# SlaveInput.net
KiCad netlist of a schematic drawn in EAGLE
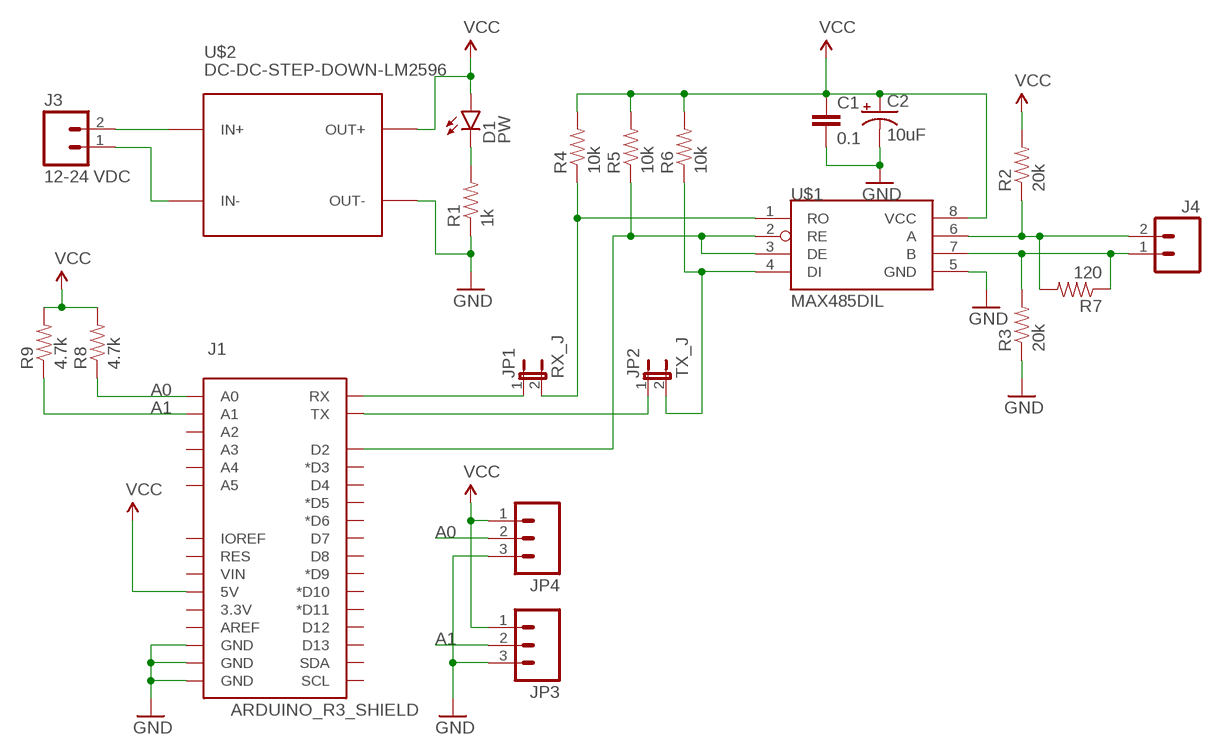
[diagram p0: schematic, sheet 1]

(export (version "E")
  (design (tool "Eeschema 10.0.6"))
  (components
    (comp (ref "C1")
      (value "0.1")
      (footprint "eagle-import:CAP-PTH-5MM")
      (libsource (lib "eagle-import") (part "CAPPTH1"))
    )
    (comp (ref "C2")
      (value "10uF")
      (footprint "eagle-import:CPOL-RADIAL-10UF-25V")
      (libsource (lib "eagle-import") (part "CAP_POLPTH2"))
    )
    (comp (ref "D1")
      (value "PW")
      (footprint "eagle-import:LED3MM")
      (libsource (lib "eagle-import") (part "LED3MM"))
    )
    (comp (ref "J1")
      (value "ARDUINO_R3_SHIELD")
      (footprint "eagle-import:UNO_R3_SHIELD")
      (libsource (lib "eagle-import") (part "ARDUINO_R3_SHIELD"))
    )
    (comp (ref "J3")
      (value "12-24 VDC")
      (footprint "eagle-import:SCREWTERMINAL-5MM-2")
      (libsource (lib "eagle-import") (part "M025MM"))
    )
    (comp (ref "J4")
      (value "M025MM")
      (footprint "eagle-import:SCREWTERMINAL-5MM-2")
      (libsource (lib "eagle-import") (part "M025MM"))
    )
    (comp (ref "JP1")
      (value "RX_J")
      (footprint "eagle-import:1X02")
      (libsource (lib "eagle-import") (part "JUMPER-2PTH"))
    )
    (comp (ref "JP2")
      (value "TX_J")
      (footprint "eagle-import:1X02")
      (libsource (lib "eagle-import") (part "JUMPER-2PTH"))
    )
    (comp (ref "JP3")
      (value "M03-SCREW-5MM")
      (footprint "eagle-import:SCREWTERMINAL-5MM-3")
      (libsource (lib "eagle-import") (part "M03-SCREW-5MM"))
    )
    (comp (ref "JP4")
      (value "M03-SCREW-5MM")
      (footprint "eagle-import:SCREWTERMINAL-5MM-3")
      (libsource (lib "eagle-import") (part "M03-SCREW-5MM"))
    )
    (comp (ref "R1")
      (value "1k")
      (footprint "eagle-import:AXIAL-0.3")
      (libsource (lib "eagle-import") (part "RESISTORAXIAL-0.3"))
    )
    (comp (ref "R2")
      (value "20k")
      (footprint "eagle-import:AXIAL-0.3")
      (libsource (lib "eagle-import") (part "RESISTORAXIAL-0.3"))
    )
    (comp (ref "R3")
      (value "20k")
      (footprint "eagle-import:AXIAL-0.3")
      (libsource (lib "eagle-import") (part "RESISTORAXIAL-0.3"))
    )
    (comp (ref "R4")
      (value "10k")
      (footprint "eagle-import:AXIAL-0.3")
      (libsource (lib "eagle-import") (part "RESISTORAXIAL-0.3"))
    )
    (comp (ref "R5")
      (value "10k")
      (footprint "eagle-import:AXIAL-0.3")
      (libsource (lib "eagle-import") (part "RESISTORAXIAL-0.3"))
    )
    (comp (ref "R6")
      (value "10k")
      (footprint "eagle-import:AXIAL-0.3")
      (libsource (lib "eagle-import") (part "RESISTORAXIAL-0.3"))
    )
    (comp (ref "R7")
      (value "120")
      (footprint "eagle-import:AXIAL-0.3")
      (libsource (lib "eagle-import") (part "RESISTORAXIAL-0.3"))
    )
    (comp (ref "R8")
      (value "4.7k")
      (footprint "eagle-import:AXIAL-0.3")
      (libsource (lib "eagle-import") (part "RESISTORAXIAL-0.3"))
    )
    (comp (ref "R9")
      (value "4.7k")
      (footprint "eagle-import:AXIAL-0.3")
      (libsource (lib "eagle-import") (part "RESISTORAXIAL-0.3"))
    )
    (comp (ref "U$1")
      (value "MAX485DIL")
      (footprint "eagle-import:DIL08")
      (libsource (lib "eagle-import") (part "MAX485DIL"))
    )
    (comp (ref "U$2")
      (value "DC-DC-STEP-DOWN-LM2596")
      (footprint "eagle-import:DC-DC-STEP-DOWN-LM2596")
      (libsource (lib "eagle-import") (part "DC-DC-STEP-DOWN-LM2596"))
    )
  )
  (nets
    (net (code "1") (name "/A0") (class "Default")
      (node (ref "J1") (pin "A0") (pinfunction "A0_A0") (pintype "bidirectional"))
      (node (ref "JP4") (pin "2") (pinfunction "2_2") (pintype "passive"))
      (node (ref "R8") (pin "P$1") (pinfunction "1_P$1") (pintype "passive"))
    )
    (net (code "2") (name "/A1") (class "Default")
      (node (ref "J1") (pin "A1") (pinfunction "A1_A1") (pintype "bidirectional"))
      (node (ref "JP3") (pin "2") (pinfunction "2_2") (pintype "passive"))
      (node (ref "R9") (pin "P$1") (pinfunction "1_P$1") (pintype "passive"))
    )
    (net (code "3") (name "GND") (class "Default")
      (node (ref "C1") (pin "2") (pinfunction "2_2") (pintype "passive"))
      (node (ref "C2") (pin "2") (pinfunction "-_2") (pintype "passive"))
      (node (ref "J1") (pin "GND@0") (pinfunction "GND_GND@0") (pintype "bidirectional"))
      (node (ref "J1") (pin "GND@1") (pinfunction "GND_GND@1") (pintype "bidirectional"))
      (node (ref "J1") (pin "GND@2") (pinfunction "GND_GND@2") (pintype "bidirectional"))
      (node (ref "JP3") (pin "3") (pinfunction "3_3") (pintype "passive"))
      (node (ref "JP4") (pin "3") (pinfunction "3_3") (pintype "passive"))
      (node (ref "R1") (pin "P$1") (pinfunction "1_P$1") (pintype "passive"))
      (node (ref "R3") (pin "P$1") (pinfunction "1_P$1") (pintype "passive"))
      (node (ref "U$1") (pin "5") (pinfunction "GND_5") (pintype "bidirectional"))
      (node (ref "U$2") (pin "OUT-") (pinfunction "OUT-_OUT-") (pintype "bidirectional"))
    )
    (net (code "4") (name "Net-(D1-C)") (class "Default")
      (node (ref "D1") (pin "K") (pinfunction "C_K") (pintype "passive"))
      (node (ref "R1") (pin "P$2") (pinfunction "2_P$2") (pintype "passive"))
    )
    (net (code "5") (name "Net-(J1-PadRX)") (class "Default")
      (node (ref "J1") (pin "RX") (pinfunction "RX_RX") (pintype "bidirectional"))
      (node (ref "JP1") (pin "1") (pinfunction "1_1") (pintype "passive"))
    )
    (net (code "6") (name "Net-(J1-PadTX)") (class "Default")
      (node (ref "J1") (pin "TX") (pinfunction "TX_TX") (pintype "bidirectional"))
      (node (ref "JP2") (pin "1") (pinfunction "1_1") (pintype "passive"))
    )
    (net (code "7") (name "Net-(J3-Pad1)") (class "Default")
      (node (ref "J3") (pin "1") (pinfunction "1_1") (pintype "passive"))
      (node (ref "U$2") (pin "IN-") (pinfunction "IN-_IN-") (pintype "bidirectional"))
    )
    (net (code "8") (name "Net-(J3-Pad2)") (class "Default")
      (node (ref "J3") (pin "2") (pinfunction "2_2") (pintype "passive"))
      (node (ref "U$2") (pin "IN+") (pinfunction "IN+_IN+") (pintype "bidirectional"))
    )
    (net (code "9") (name "Net-(R2-1)") (class "Default")
      (node (ref "J4") (pin "2") (pinfunction "2_2") (pintype "passive"))
      (node (ref "R2") (pin "P$1") (pinfunction "1_P$1") (pintype "passive"))
      (node (ref "R7") (pin "P$2") (pinfunction "2_P$2") (pintype "passive"))
      (node (ref "U$1") (pin "6") (pinfunction "A_6") (pintype "bidirectional"))
    )
    (net (code "10") (name "Net-(R3-2)") (class "Default")
      (node (ref "J4") (pin "1") (pinfunction "1_1") (pintype "passive"))
      (node (ref "R3") (pin "P$2") (pinfunction "2_P$2") (pintype "passive"))
      (node (ref "R7") (pin "P$1") (pinfunction "1_P$1") (pintype "passive"))
      (node (ref "U$1") (pin "7") (pinfunction "B_7") (pintype "bidirectional"))
    )
    (net (code "11") (name "Net-(R4-1)") (class "Default")
      (node (ref "JP1") (pin "2") (pinfunction "2_2") (pintype "passive"))
      (node (ref "R4") (pin "P$1") (pinfunction "1_P$1") (pintype "passive"))
      (node (ref "U$1") (pin "1") (pinfunction "RO_1") (pintype "bidirectional"))
    )
    (net (code "12") (name "Net-(R5-1)") (class "Default")
      (node (ref "J1") (pin "D2") (pinfunction "D2_D2") (pintype "bidirectional"))
      (node (ref "R5") (pin "P$1") (pinfunction "1_P$1") (pintype "passive"))
      (node (ref "U$1") (pin "2") (pinfunction "RE_2") (pintype "bidirectional"))
      (node (ref "U$1") (pin "3") (pinfunction "DE_3") (pintype "bidirectional"))
    )
    (net (code "13") (name "Net-(R6-1)") (class "Default")
      (node (ref "JP2") (pin "2") (pinfunction "2_2") (pintype "passive"))
      (node (ref "R6") (pin "P$1") (pinfunction "1_P$1") (pintype "passive"))
      (node (ref "U$1") (pin "4") (pinfunction "DI_4") (pintype "bidirectional"))
    )
    (net (code "14") (name "VCC") (class "Default")
      (node (ref "C1") (pin "1") (pinfunction "1_1") (pintype "passive"))
      (node (ref "C2") (pin "1") (pinfunction "+_1") (pintype "passive"))
      (node (ref "D1") (pin "A") (pinfunction "A_A") (pintype "passive"))
      (node (ref "J1") (pin "5V") (pinfunction "5V_5V") (pintype "bidirectional"))
      (node (ref "JP3") (pin "1") (pinfunction "1_1") (pintype "passive"))
      (node (ref "JP4") (pin "1") (pinfunction "1_1") (pintype "passive"))
      (node (ref "R2") (pin "P$2") (pinfunction "2_P$2") (pintype "passive"))
      (node (ref "R4") (pin "P$2") (pinfunction "2_P$2") (pintype "passive"))
      (node (ref "R5") (pin "P$2") (pinfunction "2_P$2") (pintype "passive"))
      (node (ref "R6") (pin "P$2") (pinfunction "2_P$2") (pintype "passive"))
      (node (ref "R8") (pin "P$2") (pinfunction "2_P$2") (pintype "passive"))
      (node (ref "R9") (pin "P$2") (pinfunction "2_P$2") (pintype "passive"))
      (node (ref "U$1") (pin "8") (pinfunction "VCC_8") (pintype "bidirectional"))
      (node (ref "U$2") (pin "OUT+") (pinfunction "OUT+_OUT+") (pintype "bidirectional"))
    )
    (net (code "15") (name "unconnected-(J1-*D3-PadD3)") (class "Default")
      (node (ref "J1") (pin "D3") (pinfunction "*D3_D3") (pintype "bidirectional"))
    )
    (net (code "16") (name "unconnected-(J1-*D5-PadD5)") (class "Default")
      (node (ref "J1") (pin "D5") (pinfunction "*D5_D5") (pintype "bidirectional"))
    )
    (net (code "17") (name "unconnected-(J1-*D6-PadD6)") (class "Default")
      (node (ref "J1") (pin "D6") (pinfunction "*D6_D6") (pintype "bidirectional"))
    )
    (net (code "18") (name "unconnected-(J1-*D9-PadD9)") (class "Default")
      (node (ref "J1") (pin "D9") (pinfunction "*D9_D9") (pintype "bidirectional"))
    )
    (net (code "19") (name "unconnected-(J1-*D10-PadD10)") (class "Default")
      (node (ref "J1") (pin "D10") (pinfunction "*D10_D10") (pintype "bidirectional"))
    )
    (net (code "20") (name "unconnected-(J1-*D11-PadD11)") (class "Default")
      (node (ref "J1") (pin "D11") (pinfunction "*D11_D11") (pintype "bidirectional"))
    )
    (net (code "21") (name "unconnected-(J1-Pad3.3V)") (class "Default")
      (node (ref "J1") (pin "3.3V") (pinfunction "3.3V_3.3V") (pintype "bidirectional"))
    )
    (net (code "22") (name "unconnected-(J1-PadA2)") (class "Default")
      (node (ref "J1") (pin "A2") (pinfunction "A2_A2") (pintype "bidirectional"))
    )
    (net (code "23") (name "unconnected-(J1-PadA3)") (class "Default")
      (node (ref "J1") (pin "A3") (pinfunction "A3_A3") (pintype "bidirectional"))
    )
    (net (code "24") (name "unconnected-(J1-PadA4)") (class "Default")
      (node (ref "J1") (pin "A4") (pinfunction "A4_A4") (pintype "bidirectional"))
    )
    (net (code "25") (name "unconnected-(J1-PadA5)") (class "Default")
      (node (ref "J1") (pin "A5") (pinfunction "A5_A5") (pintype "bidirectional"))
    )
    (net (code "26") (name "unconnected-(J1-PadAREF)") (class "Default")
      (node (ref "J1") (pin "AREF") (pinfunction "AREF_AREF") (pintype "bidirectional"))
    )
    (net (code "27") (name "unconnected-(J1-PadD4)") (class "Default")
      (node (ref "J1") (pin "D4") (pinfunction "D4_D4") (pintype "bidirectional"))
    )
    (net (code "28") (name "unconnected-(J1-PadD7)") (class "Default")
      (node (ref "J1") (pin "D7") (pinfunction "D7_D7") (pintype "bidirectional"))
    )
    (net (code "29") (name "unconnected-(J1-PadD8)") (class "Default")
      (node (ref "J1") (pin "D8") (pinfunction "D8_D8") (pintype "bidirectional"))
    )
    (net (code "30") (name "unconnected-(J1-PadD12)") (class "Default")
      (node (ref "J1") (pin "D12") (pinfunction "D12_D12") (pintype "bidirectional"))
    )
    (net (code "31") (name "unconnected-(J1-PadD13)") (class "Default")
      (node (ref "J1") (pin "D13") (pinfunction "D13_D13") (pintype "bidirectional"))
    )
    (net (code "32") (name "unconnected-(J1-PadIOREF)") (class "Default")
      (node (ref "J1") (pin "IOREF") (pinfunction "IOREF_IOREF") (pintype "bidirectional"))
    )
    (net (code "33") (name "unconnected-(J1-PadRES)") (class "Default")
      (node (ref "J1") (pin "RES") (pinfunction "RES_RES") (pintype "bidirectional"))
    )
    (net (code "34") (name "unconnected-(J1-PadSCL)") (class "Default")
      (node (ref "J1") (pin "SCL") (pinfunction "SCL_SCL") (pintype "bidirectional"))
    )
    (net (code "35") (name "unconnected-(J1-PadSDA)") (class "Default")
      (node (ref "J1") (pin "SDA") (pinfunction "SDA_SDA") (pintype "bidirectional"))
    )
    (net (code "36") (name "unconnected-(J1-PadVIN)") (class "Default")
      (node (ref "J1") (pin "VIN") (pinfunction "VIN_VIN") (pintype "bidirectional"))
    )
  )
)
